# CargadorMonitor.net
KiCad netlist of a schematic drawn in EAGLE
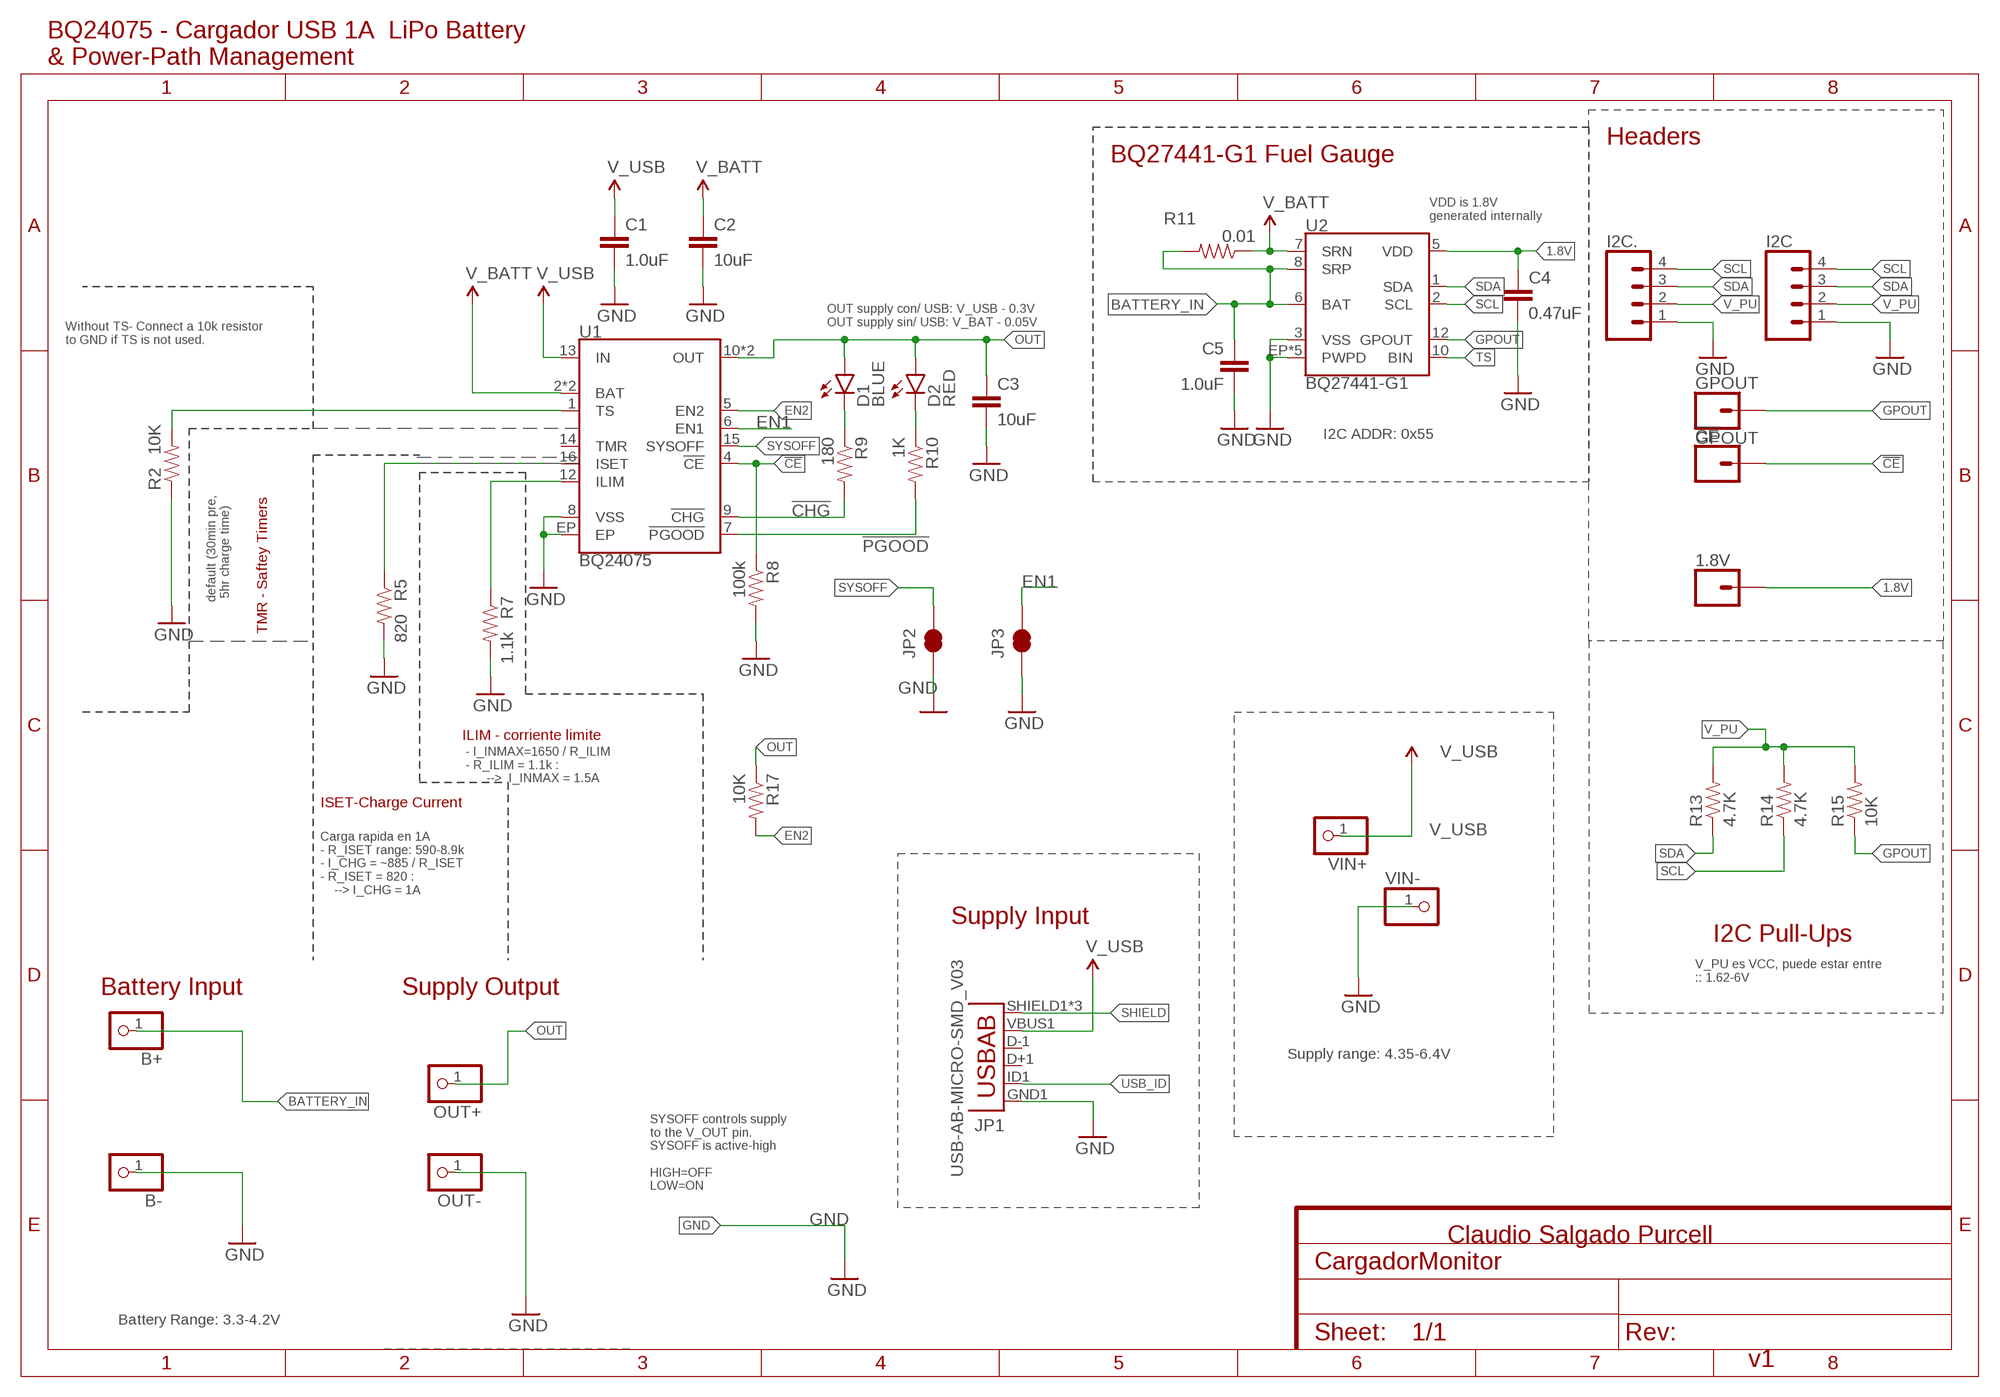
[diagram p0: schematic, sheet 1]

(export (version "E")
  (design (tool "Eeschema 10.0.6"))
  (components
    (comp (ref "!CE!")
      (value "CONN_01PTH_NO_SILK_SMALL")
      (footprint "eagle-import:1X01_SMALL")
      (libsource (lib "eagle-import") (part "CONN_01PTH_NO_SILK_SMALL"))
    )
    (comp (ref "1.8V")
      (value "CONN_01PTH_NO_SILK_SMALL")
      (footprint "eagle-import:1X01_SMALL")
      (libsource (lib "eagle-import") (part "CONN_01PTH_NO_SILK_SMALL"))
    )
    (comp (ref "B+")
      (value "PINHD-1X1")
      (footprint "eagle-import:1X01")
      (libsource (lib "eagle-import") (part "PINHD-1X1"))
    )
    (comp (ref "B-")
      (value "PINHD-1X1")
      (footprint "eagle-import:1X01")
      (libsource (lib "eagle-import") (part "PINHD-1X1"))
    )
    (comp (ref "C1")
      (value "1.0uF")
      (footprint "eagle-import:1206-CAP")
      (libsource (lib "eagle-import") (part "1.0UF50V10%(1206)"))
    )
    (comp (ref "C2")
      (value "10uF")
      (footprint "eagle-import:0805-CAP")
      (libsource (lib "eagle-import") (part "10UF10V10%(0805)"))
    )
    (comp (ref "C3")
      (value "10uF")
      (footprint "eagle-import:0805-CAP")
      (libsource (lib "eagle-import") (part "10UF10V10%(0805)"))
    )
    (comp (ref "C4")
      (value "0.47uF")
      (footprint "eagle-import:0603-CAP")
      (libsource (lib "eagle-import") (part "CAP0603-CAP"))
    )
    (comp (ref "C5")
      (value "1.0uF")
      (footprint "eagle-import:0603-CAP")
      (libsource (lib "eagle-import") (part "1.0UF-16V-10%(0603)"))
    )
    (comp (ref "D1")
      (value "BLUE")
      (footprint "eagle-import:LED-0603")
      (libsource (lib "eagle-import") (part "LED-BLUE0603"))
    )
    (comp (ref "D2")
      (value "RED")
      (footprint "eagle-import:LED-0603")
      (libsource (lib "eagle-import") (part "LED-RED0603"))
    )
    (comp (ref "GPOUT")
      (value "GPOUT")
      (footprint "eagle-import:1X01_SMALL")
      (libsource (lib "eagle-import") (part "CONN_01PTH_NO_SILK_SMALL"))
    )
    (comp (ref "I2C")
      (value "CONN_04SMD2")
      (footprint "eagle-import:JST04_1MM_RA")
      (libsource (lib "eagle-import") (part "CONN_04SMD2"))
    )
    (comp (ref "I2C.")
      (value "CONN_041.27MM")
      (footprint "eagle-import:1X04_1.27MM")
      (libsource (lib "eagle-import") (part "CONN_041.27MM"))
    )
    (comp (ref "JP1")
      (value "USB-AB-MICRO-SMD_V03")
      (footprint "eagle-import:USB-AB-MICRO-SMD_V03")
      (libsource (lib "eagle-import") (part "USB-ABCONN-11794"))
    )
    (comp (ref "JP2")
      (value "JUMPER-SMT_2_NC_TRACE_SILK")
      (footprint "eagle-import:SMT-JUMPER_2_NC_TRACE_SILK")
      (libsource (lib "eagle-import") (part "JUMPER-SMT_2_NC_TRACE_SILK"))
    )
    (comp (ref "JP3")
      (value "JUMPER-SMT_2_NC_TRACE_SILK")
      (footprint "eagle-import:SMT-JUMPER_2_NC_TRACE_SILK")
      (libsource (lib "eagle-import") (part "JUMPER-SMT_2_NC_TRACE_SILK"))
    )
    (comp (ref "OUT+")
      (value "PINHD-1X1")
      (footprint "eagle-import:1X01")
      (libsource (lib "eagle-import") (part "PINHD-1X1"))
    )
    (comp (ref "OUT-")
      (value "PINHD-1X1")
      (footprint "eagle-import:1X01")
      (libsource (lib "eagle-import") (part "PINHD-1X1"))
    )
    (comp (ref "R2")
      (value "10K")
      (footprint "eagle-import:0603-RES")
      (libsource (lib "eagle-import") (part "10KOHM-1/10W-1%(0603)0603"))
    )
    (comp (ref "R5")
      (value "820")
      (footprint "eagle-import:0603-RES")
      (libsource (lib "eagle-import") (part "RESISTOR0603-RES"))
    )
    (comp (ref "R7")
      (value "1.1k")
      (footprint "eagle-import:0603-RES")
      (libsource (lib "eagle-import") (part "RESISTOR0603-RES"))
    )
    (comp (ref "R8")
      (value "100k")
      (footprint "eagle-import:0603-RES")
      (libsource (lib "eagle-import") (part "100KOHM-1/10W-1%(0603)"))
    )
    (comp (ref "R9")
      (value "180")
      (footprint "eagle-import:0603-RES")
      (libsource (lib "eagle-import") (part "180OHM1/10W1%(0603)"))
    )
    (comp (ref "R10")
      (value "1K")
      (footprint "eagle-import:0603-RES")
      (libsource (lib "eagle-import") (part "1KOHM-1/10W-1%(0603)"))
    )
    (comp (ref "R11")
      (value "0.01")
      (footprint "eagle-import:1206")
      (libsource (lib "eagle-import") (part "SparkFun-Resistors_RESISTOR1206"))
    )
    (comp (ref "R13")
      (value "4.7K")
      (footprint "eagle-import:0603-RES")
      (libsource (lib "eagle-import") (part "4.7KOHM-1/10W-1%(0603)"))
    )
    (comp (ref "R14")
      (value "4.7K")
      (footprint "eagle-import:0603-RES")
      (libsource (lib "eagle-import") (part "4.7KOHM-1/10W-1%(0603)"))
    )
    (comp (ref "R15")
      (value "10K")
      (footprint "eagle-import:0603-RES")
      (libsource (lib "eagle-import") (part "10KOHM-1/10W-1%(0603)0603"))
    )
    (comp (ref "R17")
      (value "10K")
      (footprint "eagle-import:0603-RES")
      (libsource (lib "eagle-import") (part "10KOHM-1/10W-1%(0603)0603"))
    )
    (comp (ref "U1")
      (value "BQ24075")
      (footprint "eagle-import:PVQFN-N16")
      (fields (field (name "PROD_ID") "IC-13219"))
      (libsource (lib "eagle-import") (part "BQ24075"))
    )
    (comp (ref "U2")
      (value "BQ27441-G1")
      (footprint "eagle-import:PDSO-N12")
      (fields (field (name "PROD_ID") "IC-13220"))
      (libsource (lib "eagle-import") (part "BQ27441-G1"))
    )
    (comp (ref "VIN+")
      (value "PINHD-1X1")
      (footprint "eagle-import:1X01")
      (libsource (lib "eagle-import") (part "PINHD-1X1"))
    )
    (comp (ref "VIN-")
      (value "PINHD-1X1")
      (footprint "eagle-import:1X01")
      (libsource (lib "eagle-import") (part "PINHD-1X1"))
    )
  )
  (nets
    (net (code "1") (name "/EN1") (class "Default")
      (node (ref "JP3") (pin "2") (pinfunction "2_2") (pintype "passive"))
      (node (ref "U1") (pin "6") (pinfunction "EN1_6") (pintype "bidirectional"))
    )
    (net (code "2") (name "/~{CE}") (class "Default")
      (node (ref "!CE!") (pin "P$1") (pinfunction "1_P$1") (pintype "passive"))
      (node (ref "R8") (pin "1") (pinfunction "1_1") (pintype "passive"))
      (node (ref "U1") (pin "4") (pinfunction "~{CE}_4") (pintype "bidirectional"))
    )
    (net (code "3") (name "/~{CHG}") (class "Default")
      (node (ref "R9") (pin "2") (pinfunction "2_2") (pintype "passive"))
      (node (ref "U1") (pin "9") (pinfunction "~{CHG}_9") (pintype "bidirectional"))
    )
    (net (code "4") (name "/~{PGOOD}") (class "Default")
      (node (ref "R10") (pin "2") (pinfunction "2_2") (pintype "passive"))
      (node (ref "U1") (pin "7") (pinfunction "~{PGOOD}_7") (pintype "bidirectional"))
    )
    (net (code "5") (name "1.8V") (class "Default")
      (node (ref "1.8V") (pin "P$1") (pinfunction "1_P$1") (pintype "passive"))
      (node (ref "C4") (pin "1") (pinfunction "1_1") (pintype "passive"))
      (node (ref "U2") (pin "5") (pinfunction "VDD_5") (pintype "bidirectional"))
    )
    (net (code "6") (name "BATTERY_IN") (class "Default")
      (node (ref "B+") (pin "1") (pinfunction "1_1") (pintype "passive"))
      (node (ref "C5") (pin "1") (pinfunction "1_1") (pintype "passive"))
      (node (ref "R11") (pin "2") (pinfunction "2_2") (pintype "passive"))
      (node (ref "U2") (pin "6") (pinfunction "BAT_6") (pintype "bidirectional"))
      (node (ref "U2") (pin "8") (pinfunction "SRP_8") (pintype "bidirectional"))
    )
    (net (code "7") (name "EN2") (class "Default")
      (node (ref "R17") (pin "2") (pinfunction "2_2") (pintype "passive"))
      (node (ref "U1") (pin "5") (pinfunction "EN2_5") (pintype "bidirectional"))
    )
    (net (code "8") (name "GND") (class "Default")
      (node (ref "B-") (pin "1") (pinfunction "1_1") (pintype "passive"))
      (node (ref "C1") (pin "2") (pinfunction "2_2") (pintype "passive"))
      (node (ref "C2") (pin "2") (pinfunction "2_2") (pintype "passive"))
      (node (ref "C3") (pin "2") (pinfunction "2_2") (pintype "passive"))
      (node (ref "C4") (pin "2") (pinfunction "2_2") (pintype "passive"))
      (node (ref "C5") (pin "2") (pinfunction "2_2") (pintype "passive"))
      (node (ref "I2C") (pin "1") (pinfunction "1_1") (pintype "passive"))
      (node (ref "I2C.") (pin "1") (pinfunction "1_1") (pintype "passive"))
      (node (ref "JP1") (pin "GND1") (pinfunction "GND_GND1") (pintype "bidirectional"))
      (node (ref "JP2") (pin "1") (pinfunction "1_1") (pintype "passive"))
      (node (ref "JP3") (pin "1") (pinfunction "1_1") (pintype "passive"))
      (node (ref "OUT-") (pin "1") (pinfunction "1_1") (pintype "passive"))
      (node (ref "R2") (pin "1") (pinfunction "1_1") (pintype "passive"))
      (node (ref "R5") (pin "2") (pinfunction "2_2") (pintype "passive"))
      (node (ref "R7") (pin "2") (pinfunction "2_2") (pintype "passive"))
      (node (ref "R8") (pin "2") (pinfunction "2_2") (pintype "passive"))
      (node (ref "U1") (pin "8") (pinfunction "VSS_8") (pintype "bidirectional"))
      (node (ref "U1") (pin "EP") (pinfunction "EP_EP") (pintype "bidirectional"))
      (node (ref "U2") (pin "3") (pinfunction "VSS_3") (pintype "bidirectional"))
      (node (ref "U2") (pin "EP") (pinfunction "PWPD_EP") (pintype "bidirectional"))
      (node (ref "U2") (pin "EP1") (pinfunction "PWPD_EP1") (pintype "bidirectional"))
      (node (ref "U2") (pin "EP2") (pinfunction "PWPD_EP2") (pintype "bidirectional"))
      (node (ref "U2") (pin "EP3") (pinfunction "PWPD_EP3") (pintype "bidirectional"))
      (node (ref "U2") (pin "EP4") (pinfunction "PWPD_EP4") (pintype "bidirectional"))
      (node (ref "VIN-") (pin "1") (pinfunction "1_1") (pintype "passive"))
    )
    (net (code "9") (name "GPOUT") (class "Default")
      (node (ref "GPOUT") (pin "P$1") (pinfunction "1_P$1") (pintype "passive"))
      (node (ref "R15") (pin "1") (pinfunction "1_1") (pintype "passive"))
      (node (ref "U2") (pin "12") (pinfunction "GPOUT_12") (pintype "bidirectional"))
    )
    (net (code "10") (name "Net-(D1-PadC)") (class "Default")
      (node (ref "D1") (pin "C") (pinfunction "C_C") (pintype "passive"))
      (node (ref "R9") (pin "1") (pinfunction "1_1") (pintype "passive"))
    )
    (net (code "11") (name "Net-(D2-PadC)") (class "Default")
      (node (ref "D2") (pin "C") (pinfunction "C_C") (pintype "passive"))
      (node (ref "R10") (pin "1") (pinfunction "1_1") (pintype "passive"))
    )
    (net (code "12") (name "Net-(U1-ILIM)") (class "Default")
      (node (ref "R7") (pin "1") (pinfunction "1_1") (pintype "passive"))
      (node (ref "U1") (pin "12") (pinfunction "ILIM_12") (pintype "bidirectional"))
    )
    (net (code "13") (name "Net-(U1-ISET)") (class "Default")
      (node (ref "R5") (pin "1") (pinfunction "1_1") (pintype "passive"))
      (node (ref "U1") (pin "16") (pinfunction "ISET_16") (pintype "bidirectional"))
    )
    (net (code "14") (name "OUT") (class "Default")
      (node (ref "C3") (pin "1") (pinfunction "1_1") (pintype "passive"))
      (node (ref "D1") (pin "A") (pinfunction "A_A") (pintype "passive"))
      (node (ref "D2") (pin "A") (pinfunction "A_A") (pintype "passive"))
      (node (ref "OUT+") (pin "1") (pinfunction "1_1") (pintype "passive"))
      (node (ref "R17") (pin "1") (pinfunction "1_1") (pintype "passive"))
      (node (ref "U1") (pin "10") (pinfunction "OUT_10") (pintype "bidirectional"))
      (node (ref "U1") (pin "11") (pinfunction "OUT_11") (pintype "bidirectional"))
    )
    (net (code "15") (name "SCL") (class "Default")
      (node (ref "I2C") (pin "4") (pinfunction "4_4") (pintype "passive"))
      (node (ref "I2C.") (pin "4") (pinfunction "4_4") (pintype "passive"))
      (node (ref "R14") (pin "1") (pinfunction "1_1") (pintype "passive"))
      (node (ref "U2") (pin "2") (pinfunction "SCL_2") (pintype "bidirectional"))
    )
    (net (code "16") (name "SDA") (class "Default")
      (node (ref "I2C") (pin "3") (pinfunction "3_3") (pintype "passive"))
      (node (ref "I2C.") (pin "3") (pinfunction "3_3") (pintype "passive"))
      (node (ref "R13") (pin "1") (pinfunction "1_1") (pintype "passive"))
      (node (ref "U2") (pin "1") (pinfunction "SDA_1") (pintype "bidirectional"))
    )
    (net (code "17") (name "SHIELD") (class "Default")
      (node (ref "JP1") (pin "SHIELD1") (pinfunction "SHIELD_SHIELD1") (pintype "bidirectional"))
      (node (ref "JP1") (pin "SHIELD2") (pinfunction "SHIELD_SHIELD2") (pintype "bidirectional"))
      (node (ref "JP1") (pin "SHIELD3") (pinfunction "SHIELD_SHIELD3") (pintype "bidirectional"))
    )
    (net (code "18") (name "SYSOFF") (class "Default")
      (node (ref "JP2") (pin "2") (pinfunction "2_2") (pintype "passive"))
      (node (ref "U1") (pin "15") (pinfunction "SYSOFF_15") (pintype "bidirectional"))
    )
    (net (code "19") (name "TS") (class "Default")
      (node (ref "R2") (pin "2") (pinfunction "2_2") (pintype "passive"))
      (node (ref "U1") (pin "1") (pinfunction "TS_1") (pintype "bidirectional"))
      (node (ref "U2") (pin "10") (pinfunction "BIN_10") (pintype "bidirectional"))
    )
    (net (code "20") (name "USB_ID") (class "Default")
      (node (ref "JP1") (pin "ID1") (pinfunction "USBID_ID1") (pintype "bidirectional"))
    )
    (net (code "21") (name "V_BATT") (class "Default")
      (node (ref "C2") (pin "1") (pinfunction "1_1") (pintype "passive"))
      (node (ref "R11") (pin "1") (pinfunction "1_1") (pintype "passive"))
      (node (ref "U1") (pin "2") (pinfunction "BAT_2") (pintype "bidirectional"))
      (node (ref "U1") (pin "3") (pinfunction "BAT_3") (pintype "bidirectional"))
      (node (ref "U2") (pin "7") (pinfunction "SRN_7") (pintype "bidirectional"))
    )
    (net (code "22") (name "V_PU") (class "Default")
      (node (ref "I2C") (pin "2") (pinfunction "2_2") (pintype "passive"))
      (node (ref "I2C.") (pin "2") (pinfunction "2_2") (pintype "passive"))
      (node (ref "R13") (pin "2") (pinfunction "2_2") (pintype "passive"))
      (node (ref "R14") (pin "2") (pinfunction "2_2") (pintype "passive"))
      (node (ref "R15") (pin "2") (pinfunction "2_2") (pintype "passive"))
    )
    (net (code "23") (name "V_USB") (class "Default")
      (node (ref "C1") (pin "1") (pinfunction "1_1") (pintype "passive"))
      (node (ref "JP1") (pin "VBUS1") (pinfunction "VBUS_VBUS1") (pintype "bidirectional"))
      (node (ref "U1") (pin "13") (pinfunction "IN_13") (pintype "bidirectional"))
      (node (ref "VIN+") (pin "1") (pinfunction "1_1") (pintype "passive"))
    )
    (net (code "24") (name "unconnected-(JP1-D+-PadD+1)") (class "Default")
      (node (ref "JP1") (pin "D+1") (pinfunction "D+_D+1") (pintype "bidirectional"))
    )
    (net (code "25") (name "unconnected-(JP1-D--PadD-1)") (class "Default")
      (node (ref "JP1") (pin "D-1") (pinfunction "D-_D-1") (pintype "bidirectional"))
    )
    (net (code "26") (name "unconnected-(U1-TMR-Pad14)") (class "Default")
      (node (ref "U1") (pin "14") (pinfunction "TMR_14") (pintype "bidirectional"))
    )
  )
)
